# PROC010C_DUT_Reference.net
KiCad netlist of a schematic drawn in Altium Designer
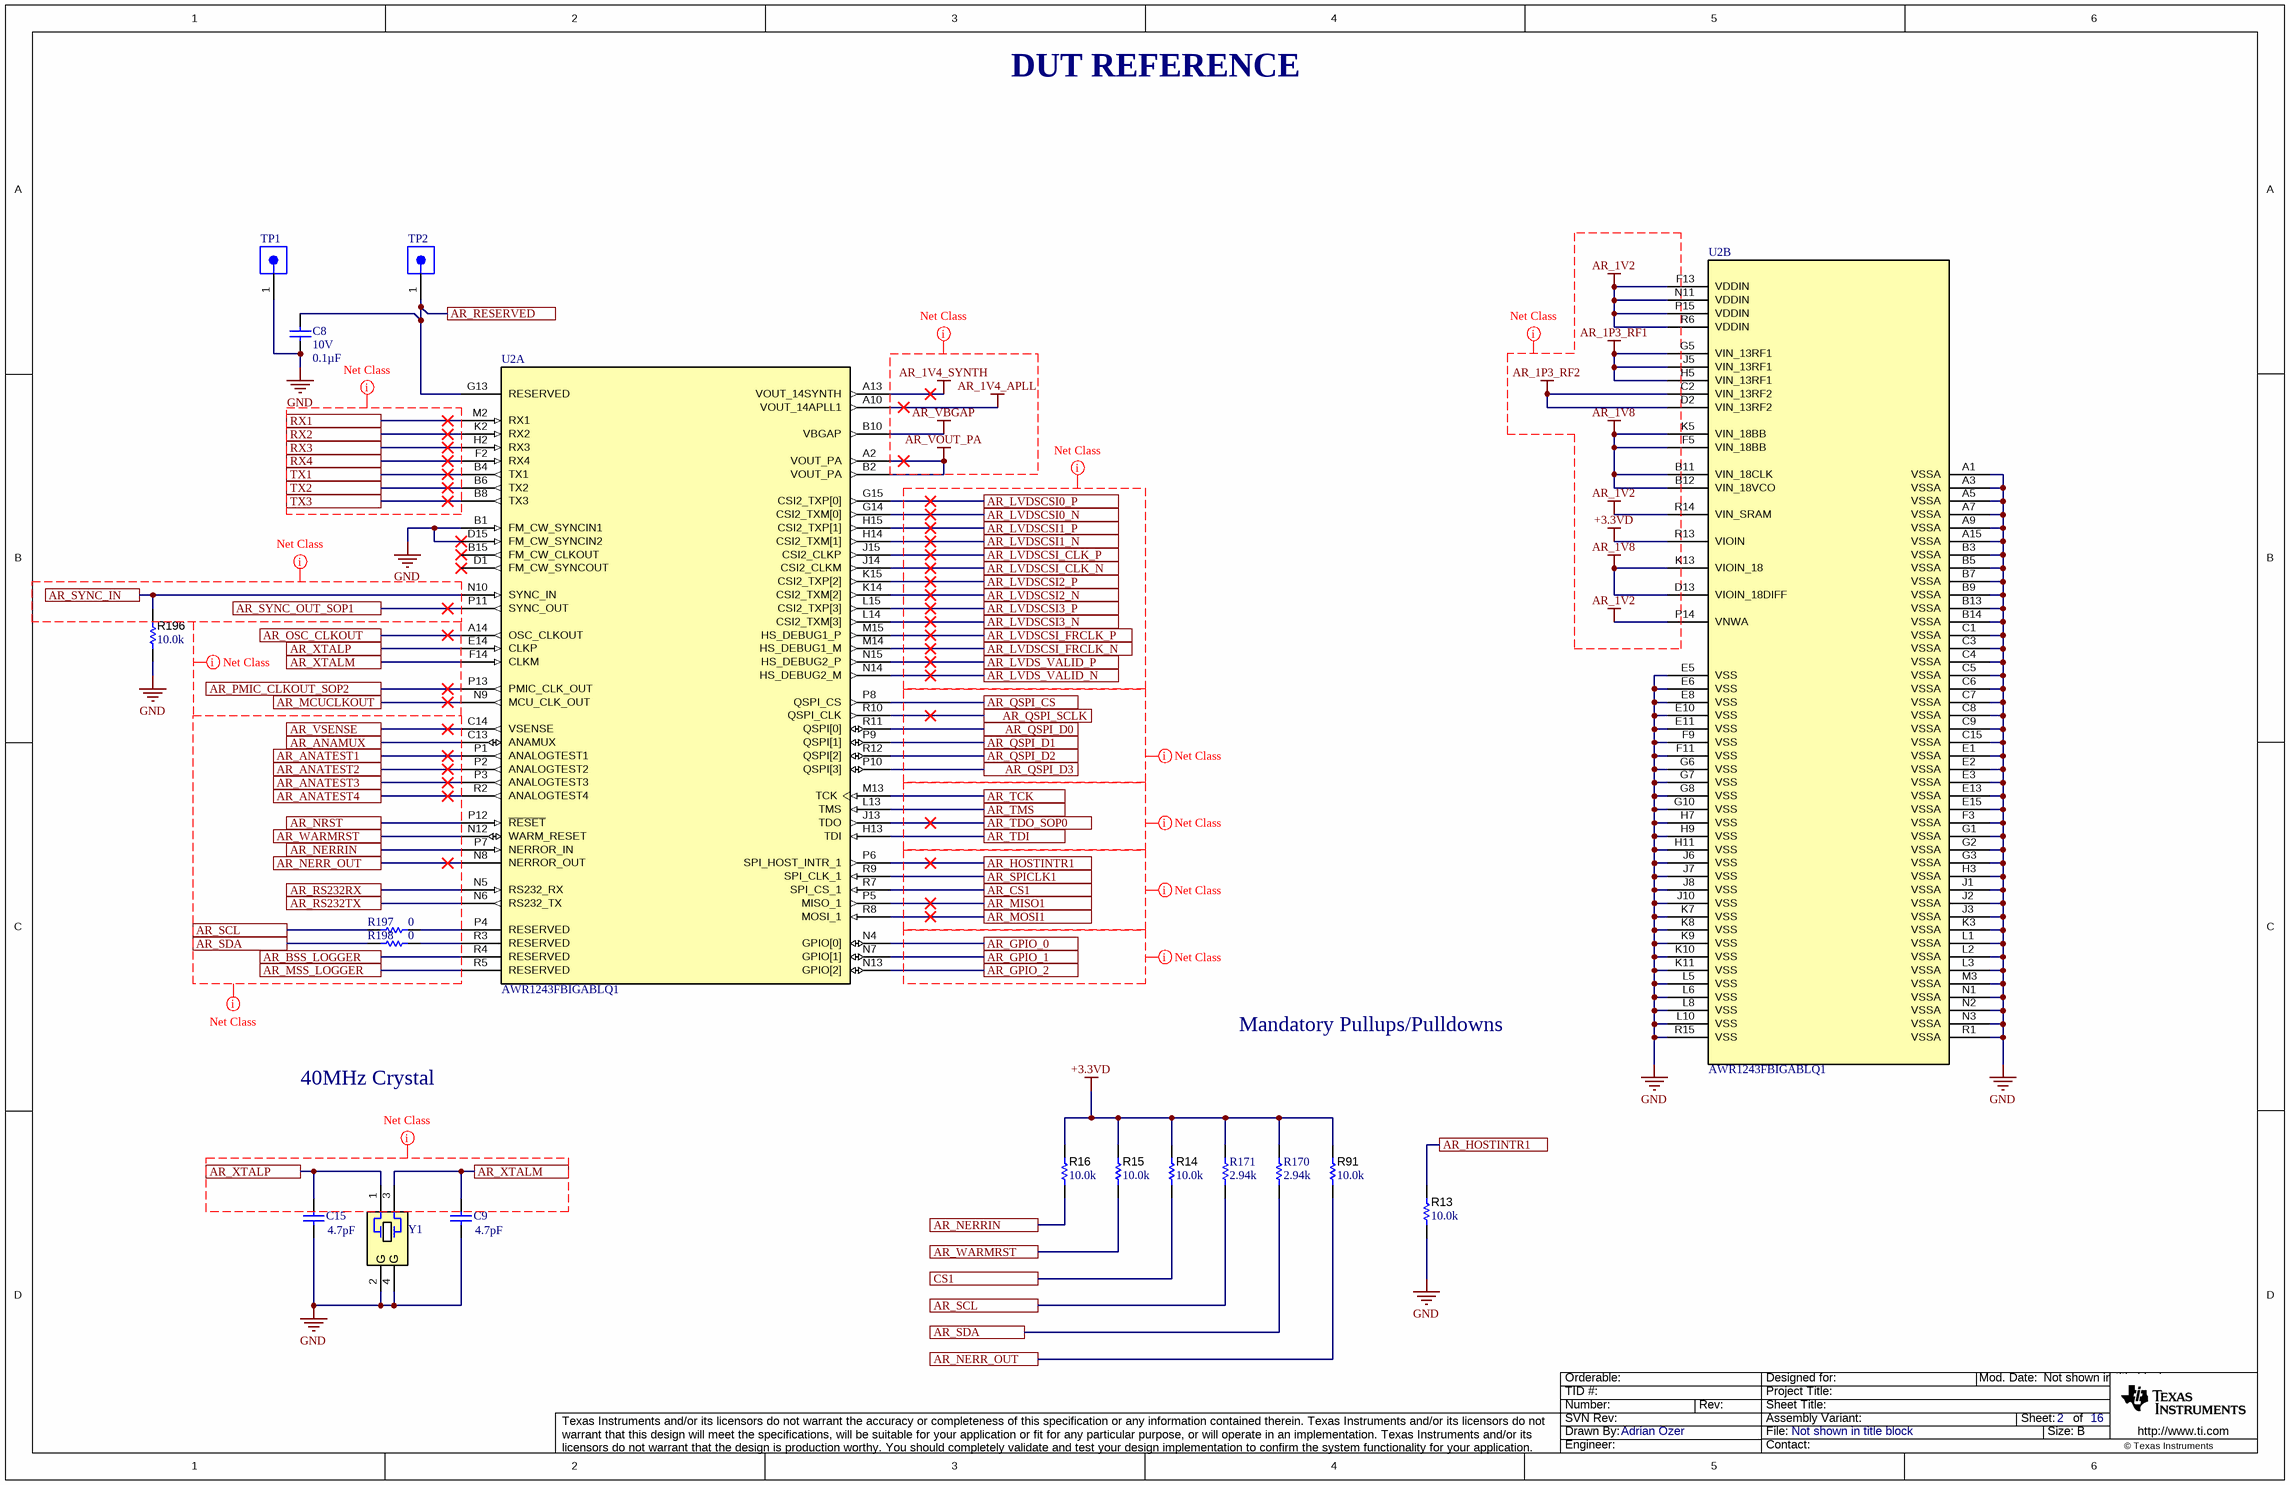
[diagram p0: PROC010C_DUT_Reference.SchDoc]

(export (version "E")
  (design (tool "Eeschema 10.0.6"))
  (components
    (comp (ref "C8")
      (value "C0603X7S1A104K030BC")
      (footprint "0201_033")
      (description "CAP, CERM, 0.1 µF, 10 V,+/- 10%, X7S, 0201")
      (fields
        (field (name "MANUFACTURER") "TDK")
        (field (name "VDC_V") "10V")
        (field (name "VALUEDISPLAYED") "0.1µF")
      )
      (libsource (lib "Altium Vault - TI") (part "Capacitor"))
    )
    (comp (ref "C9")
      (value "GJM1555C1H4R7BB01D")
      (footprint "0402")
      (description "CAP, CERM, 4.7 pF, 50 V, +/- 2%, C0G/NP0, 0402")
      (fields
        (field (name "MANUFACTURER") "MuRata")
        (field (name "VALUEDISPLAYED") "4.7pF")
        (field (name "PUBLISHER") "Texas Instruments")
      )
      (libsource (lib "Altium Vault - TI") (part "CMP-0006367-2"))
    )
    (comp (ref "C15")
      (value "GJM1555C1H4R7BB01D")
      (footprint "0402")
      (description "CAP, CERM, 4.7 pF, 50 V, +/- 2%, C0G/NP0, 0402")
      (fields
        (field (name "MANUFACTURER") "MuRata")
        (field (name "VALUEDISPLAYED") "4.7pF")
        (field (name "PUBLISHER") "Texas Instruments")
      )
      (libsource (lib "Altium Vault - TI") (part "CMP-0006367-2"))
    )
    (comp (ref "R13")
      (value "CRCW040210K0FKED")
      (footprint "0402L")
      (description "RES, 10.0 k, 1%, 0.063 W, AEC-Q200 Grade 0, 0402")
      (fields (field (name "MANUFACTURER") "Vishay-Dale") (field (name "VALUEDISPLAYED") "10.0k"))
      (libsource (lib "Altium Vault - TI") (part "Resistor"))
    )
    (comp (ref "R14")
      (value "CRCW040210K0FKED")
      (footprint "0402L")
      (description "RES, 10.0 k, 1%, 0.063 W, AEC-Q200 Grade 0, 0402")
      (fields (field (name "MANUFACTURER") "Vishay-Dale") (field (name "VALUEDISPLAYED") "10.0k"))
      (libsource (lib "Altium Vault - TI") (part "Resistor"))
    )
    (comp (ref "R15")
      (value "CRCW040210K0FKED")
      (footprint "0402L")
      (description "RES, 10.0 k, 1%, 0.063 W, AEC-Q200 Grade 0, 0402")
      (fields (field (name "MANUFACTURER") "Vishay-Dale") (field (name "VALUEDISPLAYED") "10.0k"))
      (libsource (lib "Altium Vault - TI") (part "Resistor"))
    )
    (comp (ref "R16")
      (value "CRCW040210K0FKED")
      (footprint "0402L")
      (description "RES, 10.0 k, 1%, 0.063 W, AEC-Q200 Grade 0, 0402")
      (fields (field (name "MANUFACTURER") "Vishay-Dale") (field (name "VALUEDISPLAYED") "10.0k"))
      (libsource (lib "Altium Vault - TI") (part "Resistor"))
    )
    (comp (ref "R91")
      (value "CRCW040210K0FKED")
      (footprint "0402L")
      (description "RES, 10.0 k, 1%, 0.063 W, AEC-Q200 Grade 0, 0402")
      (fields (field (name "MANUFACTURER") "Vishay-Dale") (field (name "VALUEDISPLAYED") "10.0k"))
      (libsource (lib "Altium Vault - TI") (part "Resistor"))
    )
    (comp (ref "R170")
      (value "CRCW04022K94FKED")
      (footprint "0402")
      (description "RES, 2.94 k, 1%, 0.063 W, AEC-Q200 Grade 0, 0402")
      (fields (field (name "MANUFACTURER") "Vishay-Dale") (field (name "VALUEDISPLAYED") "2.94k"))
      (libsource (lib "Altium Vault - TI") (part "Resistor"))
    )
    (comp (ref "R171")
      (value "CRCW04022K94FKED")
      (footprint "0402")
      (description "RES, 2.94 k, 1%, 0.063 W, AEC-Q200 Grade 0, 0402")
      (fields (field (name "MANUFACTURER") "Vishay-Dale") (field (name "VALUEDISPLAYED") "2.94k"))
      (libsource (lib "Altium Vault - TI") (part "Resistor"))
    )
    (comp (ref "R196")
      (value "CRCW040210K0FKED")
      (footprint "0402L")
      (description "RES, 10.0 k, 1%, 0.063 W, AEC-Q200 Grade 0, 0402")
      (fields (field (name "MANUFACTURER") "Vishay-Dale") (field (name "VALUEDISPLAYED") "10.0k"))
      (libsource (lib "Altium Vault - TI") (part "CMP-0025958-3"))
    )
    (comp (ref "R197")
      (value "CRCW02010000Z0ED")
      (footprint "0201")
      (description "RES, 0, 5%, 0.05 W, 0201")
      (fields (field (name "MANUFACTURER") "Vishay-Dale") (field (name "VALUEDISPLAYED") "0"))
      (libsource (lib "Altium Vault - TI") (part "Resistor"))
    )
    (comp (ref "R198")
      (value "CRCW02010000Z0ED")
      (footprint "0201")
      (description "RES, 0, 5%, 0.05 W, 0201")
      (fields (field (name "MANUFACTURER") "Vishay-Dale") (field (name "VALUEDISPLAYED") "0"))
      (libsource (lib "Altium Vault - TI") (part "Resistor"))
    )
    (comp (ref "TP1")
      (value "TSW-101-17-T-S")
      (footprint "Samtec_TSW-101-17-T-S")
      (description "Header, 100mil, 1x1, Tin, TH")
      (fields (field (name "MANUFACTURER") "Samtec") (field (name "PUBLISHER") "Texas Instruments"))
      (libsource (lib "Altium Vault - TI") (part "Header_1x1"))
    )
    (comp (ref "TP2")
      (value "TSW-101-17-T-S")
      (footprint "Samtec_TSW-101-17-T-S")
      (description "Header, 100mil, 1x1, Tin, TH")
      (fields (field (name "MANUFACTURER") "Samtec") (field (name "PUBLISHER") "Texas Instruments"))
      (libsource (lib "Altium Vault - TI") (part "Header_1x1"))
    )
    (comp (ref "U2")
      (value "AWR1243FBIGABLQ1")
      (footprint "ABL0161A")
      (description "Single Chip 77 and 79 GHz FMCW Transceiver, ABL0161A (FCBGA-161)")
      (fields
        (field (name "ALTERNATE PARTNUMBER") "AWR1243FBIGABLRQ1")
        (field (name "MANUFACTURER") "Texas Instruments")
        (field (name "PARTNUMBER") "AWR1243FBIGABLQ1")
      )
      (libsource (lib "Altium Vault - TI") (part "CMP-0081285-1"))
    )
    (comp (ref "Y1")
      (value "CX3225SA40000D0PTWCC")
      (footprint "Kyocera_CX3225SA")
      (description "Crystal, 40 MHz, 8pF, SMD")
      (fields (field (name "MANUFACTURER") "Kyocera"))
      (libsource (lib "Altium Vault - TI") (part "XTAL_4P_13_24OPEN"))
    )
  )
  (nets
    (net (code "1") (name "+3.3VD") (class "Default")
      (node (ref "R14") (pin "2") (pinfunction "2_2") (pintype "passive"))
      (node (ref "R15") (pin "2") (pinfunction "2_2") (pintype "passive"))
      (node (ref "R16") (pin "2") (pinfunction "2_2") (pintype "passive"))
      (node (ref "R170") (pin "2") (pinfunction "2_2") (pintype "passive"))
      (node (ref "R171") (pin "2") (pinfunction "2_2") (pintype "passive"))
      (node (ref "R91") (pin "2") (pinfunction "2_2") (pintype "passive"))
      (node (ref "U2") (pin "R13") (pinfunction "VIOIN_R13") (pintype "power_in"))
    )
    (net (code "2") (name "/AR_ANAMUX") (class "Default")
      (node (ref "U2") (pin "C13") (pinfunction "ANAMUX_C13") (pintype "bidirectional"))
    )
    (net (code "3") (name "/AR_ANATEST1") (class "Default")
      (node (ref "U2") (pin "P1") (pinfunction "ANALOGTEST1_P1") (pintype "output"))
    )
    (net (code "4") (name "/AR_ANATEST2") (class "Default")
      (node (ref "U2") (pin "P2") (pinfunction "ANALOGTEST2_P2") (pintype "output"))
    )
    (net (code "5") (name "/AR_ANATEST3") (class "Default")
      (node (ref "U2") (pin "P3") (pinfunction "ANALOGTEST3_P3") (pintype "output"))
    )
    (net (code "6") (name "/AR_ANATEST4") (class "Default")
      (node (ref "U2") (pin "R2") (pinfunction "ANALOGTEST4_R2") (pintype "output"))
    )
    (net (code "7") (name "/AR_BSS_LOGGER") (class "Default")
      (node (ref "U2") (pin "R4") (pinfunction "RESERVED_R4") (pintype "passive"))
    )
    (net (code "8") (name "/AR_CS1") (class "Default")
      (node (ref "U2") (pin "R7") (pinfunction "SPI_CS_1_R7") (pintype "input"))
    )
    (net (code "9") (name "/AR_GPIO_0") (class "Default")
      (node (ref "U2") (pin "N4") (pinfunction "GPIO[0]_N4") (pintype "bidirectional"))
    )
    (net (code "10") (name "/AR_GPIO_1") (class "Default")
      (node (ref "U2") (pin "N7") (pinfunction "GPIO[1]_N7") (pintype "bidirectional"))
    )
    (net (code "11") (name "/AR_GPIO_2") (class "Default")
      (node (ref "U2") (pin "N13") (pinfunction "GPIO[2]_N13") (pintype "bidirectional"))
    )
    (net (code "12") (name "/AR_HOSTINTR1") (class "Default")
      (node (ref "R13") (pin "2") (pinfunction "2_2") (pintype "passive"))
      (node (ref "U2") (pin "P6") (pinfunction "SPI_HOST_INTR_1_P6") (pintype "output"))
    )
    (net (code "13") (name "/AR_LVDSCSI0_N") (class "Default")
      (node (ref "U2") (pin "G14") (pinfunction "CSI2_TXM[0]_G14") (pintype "output"))
    )
    (net (code "14") (name "/AR_LVDSCSI0_P") (class "Default")
      (node (ref "U2") (pin "G15") (pinfunction "CSI2_TXP[0]_G15") (pintype "output"))
    )
    (net (code "15") (name "/AR_LVDSCSI1_N") (class "Default")
      (node (ref "U2") (pin "H14") (pinfunction "CSI2_TXM[1]_H14") (pintype "output"))
    )
    (net (code "16") (name "/AR_LVDSCSI1_P") (class "Default")
      (node (ref "U2") (pin "H15") (pinfunction "CSI2_TXP[1]_H15") (pintype "output"))
    )
    (net (code "17") (name "/AR_LVDSCSI2_N") (class "Default")
      (node (ref "U2") (pin "K14") (pinfunction "CSI2_TXM[2]_K14") (pintype "output"))
    )
    (net (code "18") (name "/AR_LVDSCSI2_P") (class "Default")
      (node (ref "U2") (pin "K15") (pinfunction "CSI2_TXP[2]_K15") (pintype "output"))
    )
    (net (code "19") (name "/AR_LVDSCSI3_N") (class "Default")
      (node (ref "U2") (pin "L14") (pinfunction "CSI2_TXM[3]_L14") (pintype "output"))
    )
    (net (code "20") (name "/AR_LVDSCSI3_P") (class "Default")
      (node (ref "U2") (pin "L15") (pinfunction "CSI2_TXP[3]_L15") (pintype "output"))
    )
    (net (code "21") (name "/AR_LVDSCSI_CLK_N") (class "Default")
      (node (ref "U2") (pin "J14") (pinfunction "CSI2_CLKM_J14") (pintype "output"))
    )
    (net (code "22") (name "/AR_LVDSCSI_CLK_P") (class "Default")
      (node (ref "U2") (pin "J15") (pinfunction "CSI2_CLKP_J15") (pintype "output"))
    )
    (net (code "23") (name "/AR_LVDSCSI_FRCLK_N") (class "Default")
      (node (ref "U2") (pin "M14") (pinfunction "HS_DEBUG1_M_M14") (pintype "output"))
    )
    (net (code "24") (name "/AR_LVDSCSI_FRCLK_P") (class "Default")
      (node (ref "U2") (pin "M15") (pinfunction "HS_DEBUG1_P_M15") (pintype "output"))
    )
    (net (code "25") (name "/AR_LVDS_VALID_N") (class "Default")
      (node (ref "U2") (pin "N14") (pinfunction "HS_DEBUG2_M_N14") (pintype "output"))
    )
    (net (code "26") (name "/AR_LVDS_VALID_P") (class "Default")
      (node (ref "U2") (pin "N15") (pinfunction "HS_DEBUG2_P_N15") (pintype "output"))
    )
    (net (code "27") (name "/AR_MCUCLKOUT") (class "Default")
      (node (ref "U2") (pin "N9") (pinfunction "MCU_CLK_OUT_N9") (pintype "output"))
    )
    (net (code "28") (name "/AR_MISO1") (class "Default")
      (node (ref "U2") (pin "P5") (pinfunction "MISO_1_P5") (pintype "output"))
    )
    (net (code "29") (name "/AR_MOSI1") (class "Default")
      (node (ref "U2") (pin "R8") (pinfunction "MOSI_1_R8") (pintype "input"))
    )
    (net (code "30") (name "/AR_MSS_LOGGER") (class "Default")
      (node (ref "U2") (pin "R5") (pinfunction "RESERVED_R5") (pintype "passive"))
    )
    (net (code "31") (name "/AR_NERRIN") (class "Default")
      (node (ref "R16") (pin "1") (pinfunction "1_1") (pintype "passive"))
      (node (ref "U2") (pin "P7") (pinfunction "NERROR_IN_P7") (pintype "input"))
    )
    (net (code "32") (name "/AR_NERR_OUT") (class "Default")
      (node (ref "R91") (pin "1") (pinfunction "1_1") (pintype "passive"))
      (node (ref "U2") (pin "N8") (pinfunction "NERROR_OUT_N8") (pintype "open_collector"))
    )
    (net (code "33") (name "/AR_NRST") (class "Default")
      (node (ref "U2") (pin "P12") (pinfunction "RESET_P12") (pintype "input"))
    )
    (net (code "34") (name "/AR_OSC_CLKOUT") (class "Default")
      (node (ref "U2") (pin "A14") (pinfunction "OSC_CLKOUT_A14") (pintype "output"))
    )
    (net (code "35") (name "/AR_PMIC_CLKOUT_SOP2") (class "Default")
      (node (ref "U2") (pin "P13") (pinfunction "PMIC_CLK_OUT_P13") (pintype "output"))
    )
    (net (code "36") (name "/AR_QSPI_CS") (class "Default")
      (node (ref "U2") (pin "P8") (pinfunction "QSPI_CS_P8") (pintype "output"))
    )
    (net (code "37") (name "/AR_QSPI_D0") (class "Default")
      (node (ref "U2") (pin "R11") (pinfunction "QSPI[0]_R11") (pintype "bidirectional"))
    )
    (net (code "38") (name "/AR_QSPI_D1") (class "Default")
      (node (ref "U2") (pin "P9") (pinfunction "QSPI[1]_P9") (pintype "bidirectional"))
    )
    (net (code "39") (name "/AR_QSPI_D2") (class "Default")
      (node (ref "U2") (pin "R12") (pinfunction "QSPI[2]_R12") (pintype "bidirectional"))
    )
    (net (code "40") (name "/AR_QSPI_D3") (class "Default")
      (node (ref "U2") (pin "P10") (pinfunction "QSPI[3]_P10") (pintype "bidirectional"))
    )
    (net (code "41") (name "/AR_QSPI_SCLK") (class "Default")
      (node (ref "U2") (pin "R10") (pinfunction "QSPI_CLK_R10") (pintype "output"))
    )
    (net (code "42") (name "/AR_RESERVED") (class "Default")
      (node (ref "C8") (pin "1") (pinfunction "1_1") (pintype "passive"))
      (node (ref "TP2") (pin "1") (pinfunction "1_1") (pintype "passive"))
      (node (ref "U2") (pin "G13") (pinfunction "RESERVED_G13") (pintype "power_in"))
    )
    (net (code "43") (name "/AR_RS232RX") (class "Default")
      (node (ref "U2") (pin "N5") (pinfunction "RS232_RX_N5") (pintype "input"))
    )
    (net (code "44") (name "/AR_RS232TX") (class "Default")
      (node (ref "U2") (pin "N6") (pinfunction "RS232_TX_N6") (pintype "output"))
    )
    (net (code "45") (name "/AR_SCL") (class "Default")
      (node (ref "R171") (pin "1") (pinfunction "1_1") (pintype "passive"))
      (node (ref "R197") (pin "1") (pinfunction "1_1") (pintype "passive"))
    )
    (net (code "46") (name "/AR_SDA") (class "Default")
      (node (ref "R170") (pin "1") (pinfunction "1_1") (pintype "passive"))
      (node (ref "R198") (pin "1") (pinfunction "1_1") (pintype "passive"))
    )
    (net (code "47") (name "/AR_SPICLK1") (class "Default")
      (node (ref "U2") (pin "R9") (pinfunction "SPI_CLK_1_R9") (pintype "input"))
    )
    (net (code "48") (name "/AR_SYNC_IN") (class "Default")
      (node (ref "R196") (pin "2") (pinfunction "2_2") (pintype "passive"))
      (node (ref "U2") (pin "N10") (pinfunction "SYNC_IN_N10") (pintype "input"))
    )
    (net (code "49") (name "/AR_SYNC_OUT_SOP1") (class "Default")
      (node (ref "U2") (pin "P11") (pinfunction "SYNC_OUT_P11") (pintype "output"))
    )
    (net (code "50") (name "/AR_TCK") (class "Default")
      (node (ref "U2") (pin "M13") (pinfunction "TCK_M13") (pintype "input"))
    )
    (net (code "51") (name "/AR_TDI") (class "Default")
      (node (ref "U2") (pin "H13") (pinfunction "TDI_H13") (pintype "input"))
    )
    (net (code "52") (name "/AR_TDO_SOP0") (class "Default")
      (node (ref "U2") (pin "J13") (pinfunction "TDO_J13") (pintype "output"))
    )
    (net (code "53") (name "/AR_TMS") (class "Default")
      (node (ref "U2") (pin "L13") (pinfunction "TMS_L13") (pintype "input"))
    )
    (net (code "54") (name "/AR_VSENSE") (class "Default")
      (node (ref "U2") (pin "C14") (pinfunction "VSENSE_C14") (pintype "output"))
    )
    (net (code "55") (name "/AR_WARMRST") (class "Default")
      (node (ref "R15") (pin "1") (pinfunction "1_1") (pintype "passive"))
      (node (ref "U2") (pin "N12") (pinfunction "WARM_RESET_N12") (pintype "bidirectional"))
    )
    (net (code "56") (name "/AR_XTALM") (class "Default")
      (node (ref "C9") (pin "1") (pinfunction "1_1") (pintype "passive"))
      (node (ref "U2") (pin "F14") (pinfunction "CLKM_F14") (pintype "input"))
      (node (ref "Y1") (pin "3") (pinfunction "3_3") (pintype "passive"))
    )
    (net (code "57") (name "/AR_XTALP") (class "Default")
      (node (ref "C15") (pin "2") (pinfunction "2_2") (pintype "passive"))
      (node (ref "U2") (pin "E14") (pinfunction "CLKP_E14") (pintype "input"))
      (node (ref "Y1") (pin "1") (pinfunction "1_1") (pintype "passive"))
    )
    (net (code "58") (name "/CS1") (class "Default")
      (node (ref "R14") (pin "1") (pinfunction "1_1") (pintype "passive"))
    )
    (net (code "59") (name "/RX1") (class "Default")
      (node (ref "U2") (pin "M2") (pinfunction "RX1_M2") (pintype "input"))
    )
    (net (code "60") (name "/RX2") (class "Default")
      (node (ref "U2") (pin "K2") (pinfunction "RX2_K2") (pintype "input"))
    )
    (net (code "61") (name "/RX3") (class "Default")
      (node (ref "U2") (pin "H2") (pinfunction "RX3_H2") (pintype "input"))
    )
    (net (code "62") (name "/RX4") (class "Default")
      (node (ref "U2") (pin "F2") (pinfunction "RX4_F2") (pintype "input"))
    )
    (net (code "63") (name "/TX1") (class "Default")
      (node (ref "U2") (pin "B4") (pinfunction "TX1_B4") (pintype "output"))
    )
    (net (code "64") (name "/TX2") (class "Default")
      (node (ref "U2") (pin "B6") (pinfunction "TX2_B6") (pintype "output"))
    )
    (net (code "65") (name "/TX3") (class "Default")
      (node (ref "U2") (pin "B8") (pinfunction "TX3_B8") (pintype "output"))
    )
    (net (code "66") (name "AR_1P3_RF1") (class "Default")
      (node (ref "U2") (pin "G5") (pinfunction "VIN_13RF1_G5") (pintype "power_in"))
      (node (ref "U2") (pin "H5") (pinfunction "VIN_13RF1_H5") (pintype "power_in"))
      (node (ref "U2") (pin "J5") (pinfunction "VIN_13RF1_J5") (pintype "power_in"))
    )
    (net (code "67") (name "AR_1P3_RF2") (class "Default")
      (node (ref "U2") (pin "C2") (pinfunction "VIN_13RF2_C2") (pintype "power_in"))
      (node (ref "U2") (pin "D2") (pinfunction "VIN_13RF2_D2") (pintype "power_in"))
    )
    (net (code "68") (name "AR_1V2") (class "Default")
      (node (ref "U2") (pin "F13") (pinfunction "VDDIN_F13") (pintype "power_in"))
      (node (ref "U2") (pin "N11") (pinfunction "VDDIN_N11") (pintype "power_in"))
      (node (ref "U2") (pin "P14") (pinfunction "VNWA_P14") (pintype "power_in"))
      (node (ref "U2") (pin "P15") (pinfunction "VDDIN_P15") (pintype "power_in"))
      (node (ref "U2") (pin "R14") (pinfunction "VIN_SRAM_R14") (pintype "power_in"))
      (node (ref "U2") (pin "R6") (pinfunction "VDDIN_R6") (pintype "power_in"))
    )
    (net (code "69") (name "AR_1V4_APLL") (class "Default")
      (node (ref "U2") (pin "A10") (pinfunction "VOUT_14APLL1_A10") (pintype "output"))
    )
    (net (code "70") (name "AR_1V4_SYNTH") (class "Default")
      (node (ref "U2") (pin "A13") (pinfunction "VOUT_14SYNTH_A13") (pintype "output"))
    )
    (net (code "71") (name "AR_1V8") (class "Default")
      (node (ref "U2") (pin "B11") (pinfunction "VIN_18CLK_B11") (pintype "power_in"))
      (node (ref "U2") (pin "B12") (pinfunction "VIN_18VCO_B12") (pintype "power_in"))
      (node (ref "U2") (pin "D13") (pinfunction "VIOIN_18DIFF_D13") (pintype "power_in"))
      (node (ref "U2") (pin "F5") (pinfunction "VIN_18BB_F5") (pintype "power_in"))
      (node (ref "U2") (pin "K13") (pinfunction "VIOIN_18_K13") (pintype "power_in"))
      (node (ref "U2") (pin "K5") (pinfunction "VIN_18BB_K5") (pintype "power_in"))
    )
    (net (code "72") (name "AR_VBGAP") (class "Default")
      (node (ref "U2") (pin "B10") (pinfunction "VBGAP_B10") (pintype "output"))
    )
    (net (code "73") (name "AR_VOUT_PA") (class "Default")
      (node (ref "U2") (pin "A2") (pinfunction "VOUT_PA_A2") (pintype "output"))
      (node (ref "U2") (pin "B2") (pinfunction "VOUT_PA_B2") (pintype "output"))
    )
    (net (code "74") (name "GND") (class "Default")
      (node (ref "C15") (pin "1") (pinfunction "1_1") (pintype "passive"))
      (node (ref "C8") (pin "2") (pinfunction "2_2") (pintype "passive"))
      (node (ref "C9") (pin "2") (pinfunction "2_2") (pintype "passive"))
      (node (ref "R13") (pin "1") (pinfunction "1_1") (pintype "passive"))
      (node (ref "R196") (pin "1") (pinfunction "1_1") (pintype "passive"))
      (node (ref "TP1") (pin "1") (pinfunction "1_1") (pintype "passive"))
      (node (ref "U2") (pin "A1") (pinfunction "VSSA_A1") (pintype "power_in"))
      (node (ref "U2") (pin "A15") (pinfunction "VSSA_A15") (pintype "power_in"))
      (node (ref "U2") (pin "A3") (pinfunction "VSSA_A3") (pintype "power_in"))
      (node (ref "U2") (pin "A5") (pinfunction "VSSA_A5") (pintype "power_in"))
      (node (ref "U2") (pin "A7") (pinfunction "VSSA_A7") (pintype "power_in"))
      (node (ref "U2") (pin "A9") (pinfunction "VSSA_A9") (pintype "power_in"))
      (node (ref "U2") (pin "B1") (pinfunction "FM_CW_SYNCIN1_B1") (pintype "input"))
      (node (ref "U2") (pin "B13") (pinfunction "VSSA_B13") (pintype "power_in"))
      (node (ref "U2") (pin "B14") (pinfunction "VSSA_B14") (pintype "power_in"))
      (node (ref "U2") (pin "B3") (pinfunction "VSSA_B3") (pintype "power_in"))
      (node (ref "U2") (pin "B5") (pinfunction "VSSA_B5") (pintype "power_in"))
      (node (ref "U2") (pin "B7") (pinfunction "VSSA_B7") (pintype "power_in"))
      (node (ref "U2") (pin "B9") (pinfunction "VSSA_B9") (pintype "power_in"))
      (node (ref "U2") (pin "C1") (pinfunction "VSSA_C1") (pintype "power_in"))
      (node (ref "U2") (pin "C15") (pinfunction "VSSA_C15") (pintype "power_in"))
      (node (ref "U2") (pin "C3") (pinfunction "VSSA_C3") (pintype "power_in"))
      (node (ref "U2") (pin "C4") (pinfunction "VSSA_C4") (pintype "power_in"))
      (node (ref "U2") (pin "C5") (pinfunction "VSSA_C5") (pintype "power_in"))
      (node (ref "U2") (pin "C6") (pinfunction "VSSA_C6") (pintype "power_in"))
      (node (ref "U2") (pin "C7") (pinfunction "VSSA_C7") (pintype "power_in"))
      (node (ref "U2") (pin "C8") (pinfunction "VSSA_C8") (pintype "power_in"))
      (node (ref "U2") (pin "C9") (pinfunction "VSSA_C9") (pintype "power_in"))
      (node (ref "U2") (pin "D15") (pinfunction "FM_CW_SYNCIN2_D15") (pintype "input"))
      (node (ref "U2") (pin "E1") (pinfunction "VSSA_E1") (pintype "power_in"))
      (node (ref "U2") (pin "E10") (pinfunction "VSS_E10") (pintype "power_in"))
      (node (ref "U2") (pin "E11") (pinfunction "VSS_E11") (pintype "power_in"))
      (node (ref "U2") (pin "E13") (pinfunction "VSSA_E13") (pintype "power_in"))
      (node (ref "U2") (pin "E15") (pinfunction "VSSA_E15") (pintype "power_in"))
      (node (ref "U2") (pin "E2") (pinfunction "VSSA_E2") (pintype "power_in"))
      (node (ref "U2") (pin "E3") (pinfunction "VSSA_E3") (pintype "power_in"))
      (node (ref "U2") (pin "E5") (pinfunction "VSS_E5") (pintype "power_in"))
      (node (ref "U2") (pin "E6") (pinfunction "VSS_E6") (pintype "power_in"))
      (node (ref "U2") (pin "E8") (pinfunction "VSS_E8") (pintype "power_in"))
      (node (ref "U2") (pin "F11") (pinfunction "VSS_F11") (pintype "power_in"))
      (node (ref "U2") (pin "F3") (pinfunction "VSSA_F3") (pintype "power_in"))
      (node (ref "U2") (pin "F9") (pinfunction "VSS_F9") (pintype "power_in"))
      (node (ref "U2") (pin "G1") (pinfunction "VSSA_G1") (pintype "power_in"))
      (node (ref "U2") (pin "G10") (pinfunction "VSS_G10") (pintype "power_in"))
      (node (ref "U2") (pin "G2") (pinfunction "VSSA_G2") (pintype "power_in"))
      (node (ref "U2") (pin "G3") (pinfunction "VSSA_G3") (pintype "power_in"))
      (node (ref "U2") (pin "G6") (pinfunction "VSS_G6") (pintype "power_in"))
      (node (ref "U2") (pin "G7") (pinfunction "VSS_G7") (pintype "power_in"))
      (node (ref "U2") (pin "G8") (pinfunction "VSS_G8") (pintype "power_in"))
      (node (ref "U2") (pin "H11") (pinfunction "VSS_H11") (pintype "power_in"))
      (node (ref "U2") (pin "H3") (pinfunction "VSSA_H3") (pintype "power_in"))
      (node (ref "U2") (pin "H7") (pinfunction "VSS_H7") (pintype "power_in"))
      (node (ref "U2") (pin "H9") (pinfunction "VSS_H9") (pintype "power_in"))
      (node (ref "U2") (pin "J1") (pinfunction "VSSA_J1") (pintype "power_in"))
      (node (ref "U2") (pin "J10") (pinfunction "VSS_J10") (pintype "power_in"))
      (node (ref "U2") (pin "J2") (pinfunction "VSSA_J2") (pintype "power_in"))
      (node (ref "U2") (pin "J3") (pinfunction "VSSA_J3") (pintype "power_in"))
      (node (ref "U2") (pin "J6") (pinfunction "VSS_J6") (pintype "power_in"))
      (node (ref "U2") (pin "J7") (pinfunction "VSS_J7") (pintype "power_in"))
      (node (ref "U2") (pin "J8") (pinfunction "VSS_J8") (pintype "power_in"))
      (node (ref "U2") (pin "K10") (pinfunction "VSS_K10") (pintype "power_in"))
      (node (ref "U2") (pin "K11") (pinfunction "VSS_K11") (pintype "power_in"))
      (node (ref "U2") (pin "K3") (pinfunction "VSSA_K3") (pintype "power_in"))
      (node (ref "U2") (pin "K7") (pinfunction "VSS_K7") (pintype "power_in"))
      (node (ref "U2") (pin "K8") (pinfunction "VSS_K8") (pintype "power_in"))
      (node (ref "U2") (pin "K9") (pinfunction "VSS_K9") (pintype "power_in"))
      (node (ref "U2") (pin "L1") (pinfunction "VSSA_L1") (pintype "power_in"))
      (node (ref "U2") (pin "L10") (pinfunction "VSS_L10") (pintype "power_in"))
      (node (ref "U2") (pin "L2") (pinfunction "VSSA_L2") (pintype "power_in"))
      (node (ref "U2") (pin "L3") (pinfunction "VSSA_L3") (pintype "power_in"))
      (node (ref "U2") (pin "L5") (pinfunction "VSS_L5") (pintype "power_in"))
      (node (ref "U2") (pin "L6") (pinfunction "VSS_L6") (pintype "power_in"))
      (node (ref "U2") (pin "L8") (pinfunction "VSS_L8") (pintype "power_in"))
      (node (ref "U2") (pin "M3") (pinfunction "VSSA_M3") (pintype "power_in"))
      (node (ref "U2") (pin "N1") (pinfunction "VSSA_N1") (pintype "power_in"))
      (node (ref "U2") (pin "N2") (pinfunction "VSSA_N2") (pintype "power_in"))
      (node (ref "U2") (pin "N3") (pinfunction "VSSA_N3") (pintype "power_in"))
      (node (ref "U2") (pin "R1") (pinfunction "VSSA_R1") (pintype "power_in"))
      (node (ref "U2") (pin "R15") (pinfunction "VSS_R15") (pintype "power_in"))
      (node (ref "Y1") (pin "2") (pinfunction "GND_2") (pintype "power_in"))
      (node (ref "Y1") (pin "4") (pinfunction "GND_4") (pintype "power_in"))
    )
    (net (code "75") (name "Net-(R197-Pad2)") (class "Default")
      (node (ref "R197") (pin "2") (pinfunction "2_2") (pintype "passive"))
      (node (ref "U2") (pin "P4") (pinfunction "RESERVED_P4") (pintype "passive"))
    )
    (net (code "76") (name "Net-(R198-Pad2)") (class "Default")
      (node (ref "R198") (pin "2") (pinfunction "2_2") (pintype "passive"))
      (node (ref "U2") (pin "R3") (pinfunction "RESERVED_R3") (pintype "passive"))
    )
    (net (code "77") (name "unconnected-(U2A-FM_CW_CLKOUT-PadB15)") (class "Default")
      (node (ref "U2") (pin "B15") (pinfunction "FM_CW_CLKOUT_B15") (pintype "output+no_connect"))
    )
    (net (code "78") (name "unconnected-(U2A-FM_CW_SYNCOUT-PadD1)") (class "Default")
      (node (ref "U2") (pin "D1") (pinfunction "FM_CW_SYNCOUT_D1") (pintype "output+no_connect"))
    )
  )
)
